# SW6124_A_B_C_MCU_SEG.net
KiCad netlist of a schematic drawn in Altium Designer
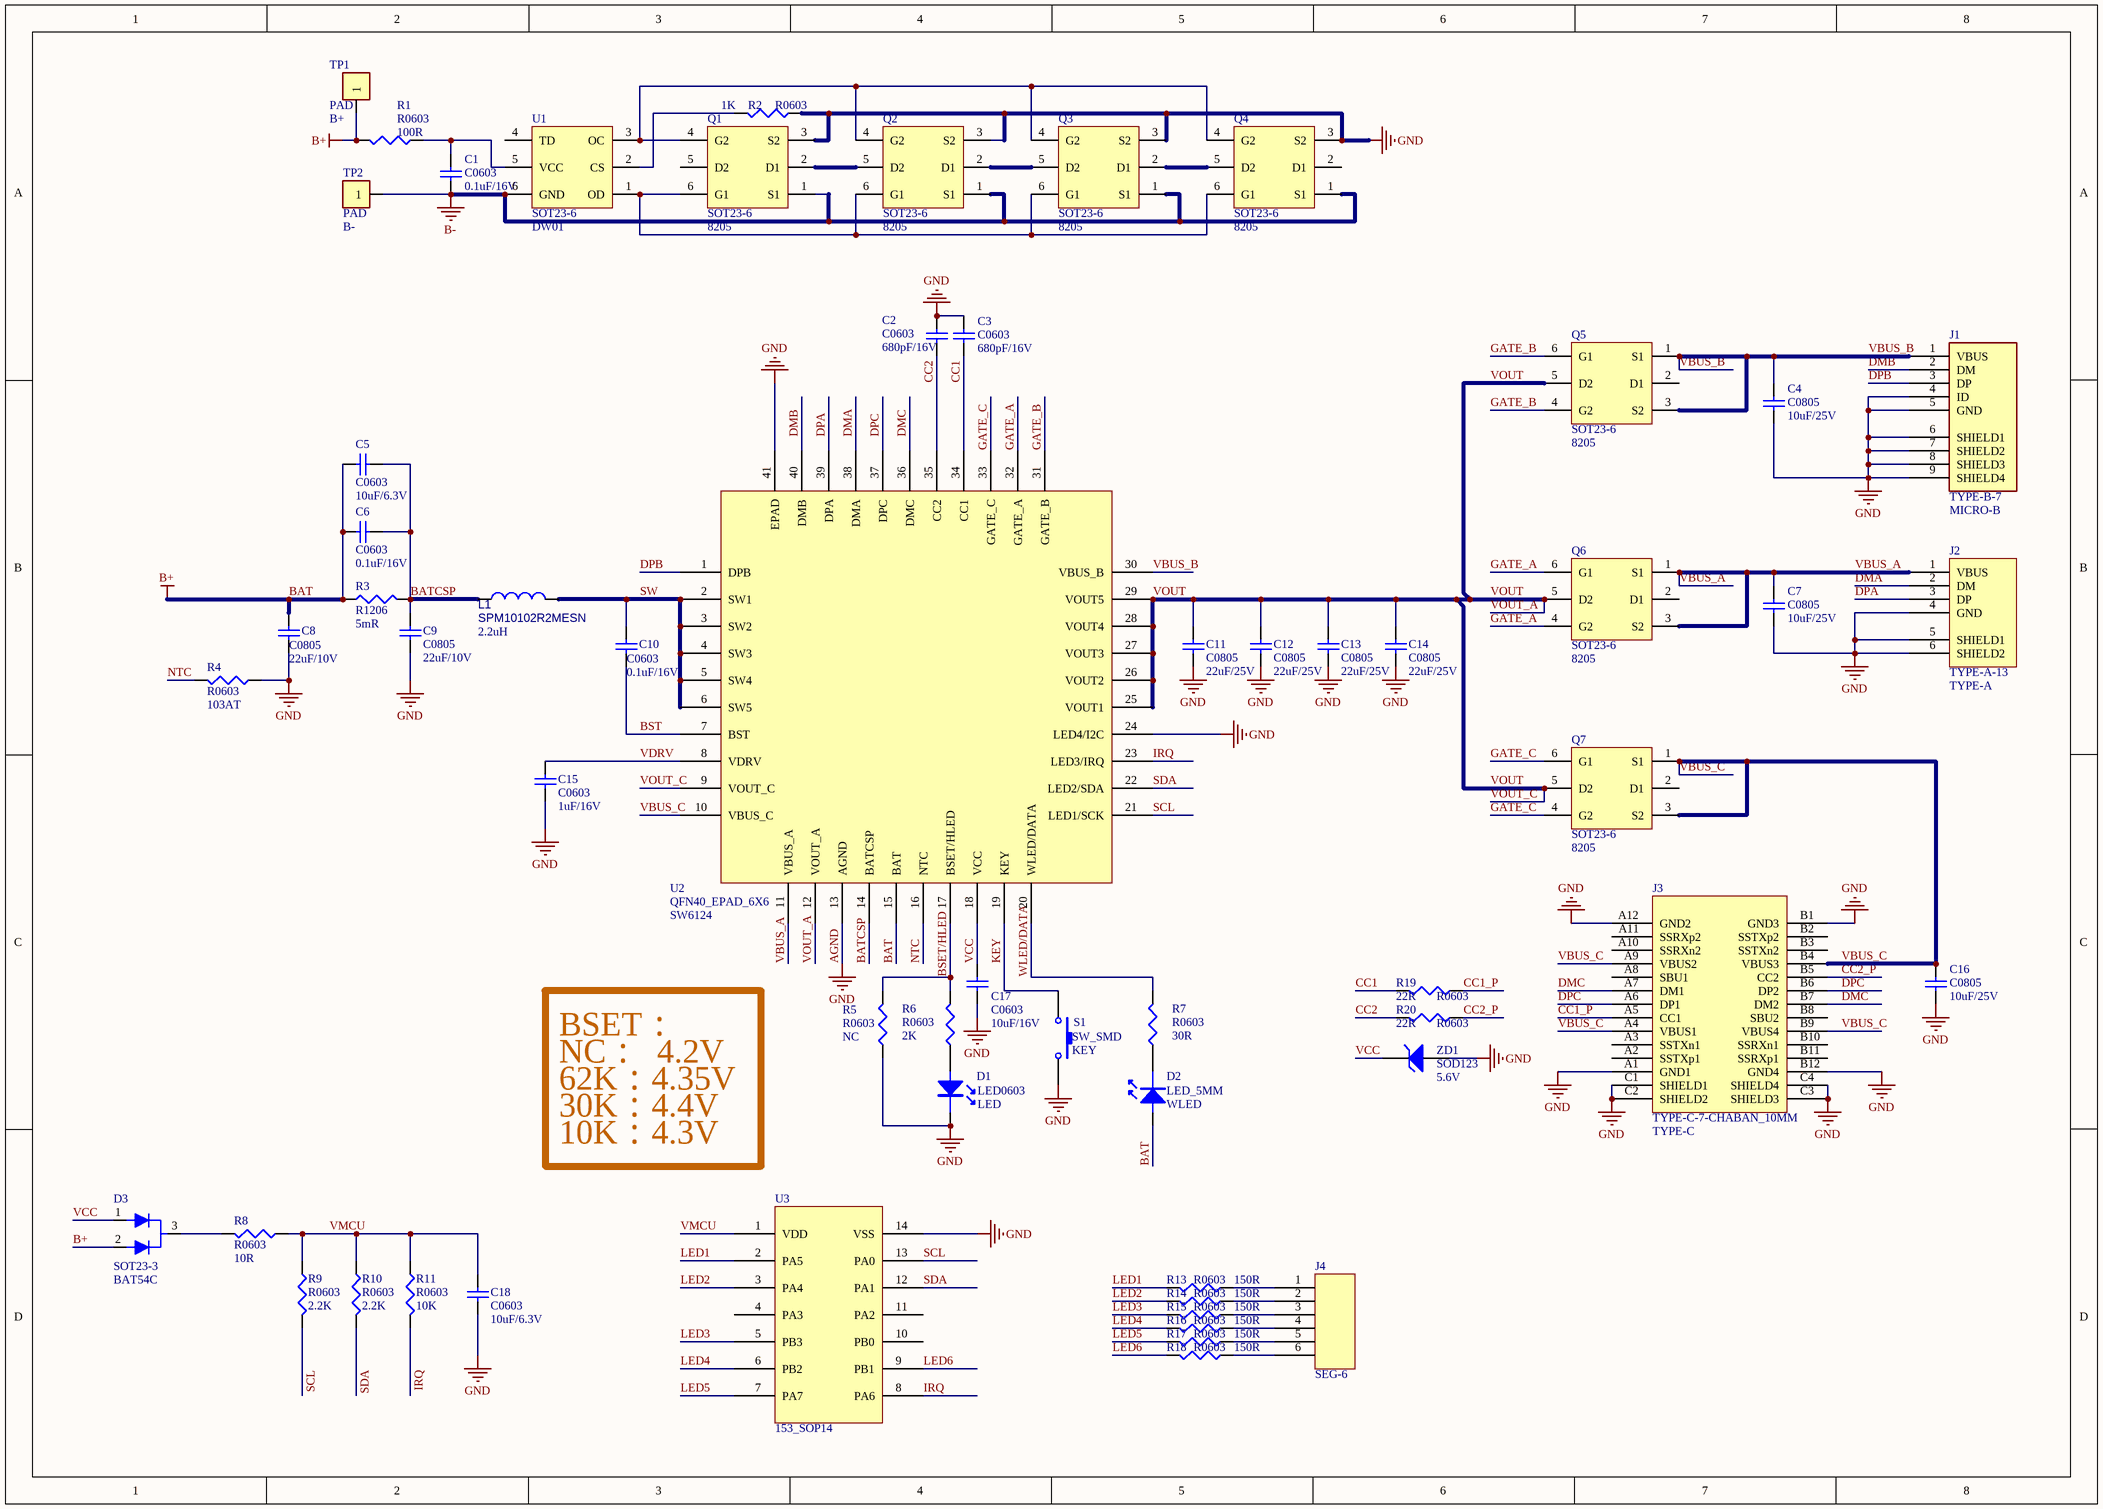
[diagram p0: SW6124+A+B+C+MCU+SEG.SchDoc]

(export (version "E")
  (design (tool "Eeschema 10.0.6"))
  (components
    (comp (ref "C1")
      (value "C0603")
      (footprint "C0603")
      (description "Capacitor")
      (fields (field (name "ALTIUM_VALUE") "0.1uF/16V") (field (name "PUBLISHER") "Altium Limited"))
      (libsource (lib "*") (part "Cap"))
    )
    (comp (ref "C2")
      (value "C0603")
      (footprint "C0603")
      (description "Capacitor")
      (fields (field (name "ALTIUM_VALUE") "680pF/16V") (field (name "PUBLISHER") "Altium Limited"))
      (libsource (lib "*") (part "CAP0603"))
    )
    (comp (ref "C3")
      (value "C0603")
      (footprint "C0603")
      (description "Capacitor")
      (fields (field (name "ALTIUM_VALUE") "680pF/16V") (field (name "PUBLISHER") "Altium Limited"))
      (libsource (lib "*") (part "CAP0603"))
    )
    (comp (ref "C4")
      (value "C0805")
      (footprint "C0805")
      (description "Capacitor")
      (fields (field (name "ALTIUM_VALUE") "10uF/25V") (field (name "PUBLISHER") "Altium Limited"))
      (libsource (lib "*") (part "CAP0603"))
    )
    (comp (ref "C5")
      (value "C0603")
      (footprint "C0603")
      (description "Capacitor")
      (fields (field (name "ALTIUM_VALUE") "10uF/6.3V") (field (name "PUBLISHER") "Altium Limited"))
      (libsource (lib "*") (part "CAP0603"))
    )
    (comp (ref "C6")
      (value "C0603")
      (footprint "C0603")
      (description "Capacitor")
      (fields (field (name "ALTIUM_VALUE") "0.1uF/16V") (field (name "PUBLISHER") "Altium Limited"))
      (libsource (lib "*") (part "CAP0603"))
    )
    (comp (ref "C7")
      (value "C0805")
      (footprint "C0805")
      (description "Capacitor")
      (fields (field (name "ALTIUM_VALUE") "10uF/25V") (field (name "PUBLISHER") "Altium Limited"))
      (libsource (lib "*") (part "CAP0603"))
    )
    (comp (ref "C8")
      (value "C0805")
      (footprint "C0805")
      (description "Capacitor")
      (fields (field (name "ALTIUM_VALUE") "22uF/10V") (field (name "PUBLISHER") "Altium Limited"))
      (libsource (lib "*") (part "CAP0805"))
    )
    (comp (ref "C9")
      (value "C0805")
      (footprint "C0805")
      (description "Capacitor")
      (fields (field (name "ALTIUM_VALUE") "22uF/10V") (field (name "PUBLISHER") "Altium Limited"))
      (libsource (lib "*") (part "CAP0805"))
    )
    (comp (ref "C10")
      (value "C0603")
      (footprint "C0603")
      (description "Capacitor")
      (fields (field (name "ALTIUM_VALUE") "0.1uF/16V") (field (name "PUBLISHER") "Altium Limited"))
      (libsource (lib "*") (part "CAP0603"))
    )
    (comp (ref "C11")
      (value "C0805")
      (footprint "C0805")
      (description "Capacitor")
      (fields (field (name "ALTIUM_VALUE") "22uF/25V") (field (name "PUBLISHER") "Altium Limited"))
      (libsource (lib "*") (part "CAP0805"))
    )
    (comp (ref "C12")
      (value "C0805")
      (footprint "C0805")
      (description "Capacitor")
      (fields (field (name "ALTIUM_VALUE") "22uF/25V") (field (name "PUBLISHER") "Altium Limited"))
      (libsource (lib "*") (part "CAP0805"))
    )
    (comp (ref "C13")
      (value "C0805")
      (footprint "C0805")
      (description "Capacitor")
      (fields (field (name "ALTIUM_VALUE") "22uF/25V") (field (name "PUBLISHER") "Altium Limited"))
      (libsource (lib "*") (part "CAP0805"))
    )
    (comp (ref "C14")
      (value "C0805")
      (footprint "C0805")
      (description "Capacitor")
      (fields (field (name "ALTIUM_VALUE") "22uF/25V") (field (name "PUBLISHER") "Altium Limited"))
      (libsource (lib "*") (part "CAP0805"))
    )
    (comp (ref "C15")
      (value "C0603")
      (footprint "C0603")
      (description "Capacitor")
      (fields (field (name "ALTIUM_VALUE") "1uF/16V") (field (name "PUBLISHER") "Altium Limited"))
      (libsource (lib "*") (part "CAP0603"))
    )
    (comp (ref "C16")
      (value "C0805")
      (footprint "C0805")
      (description "Capacitor")
      (fields (field (name "ALTIUM_VALUE") "10uF/25V") (field (name "PUBLISHER") "Altium Limited"))
      (libsource (lib "*") (part "CAP0603"))
    )
    (comp (ref "C17")
      (value "C0603")
      (footprint "C0603")
      (description "Capacitor")
      (fields (field (name "ALTIUM_VALUE") "10uF/16V") (field (name "PUBLISHER") "Altium Limited"))
      (libsource (lib "*") (part "CAP0603"))
    )
    (comp (ref "C18")
      (value "C0603")
      (footprint "C0603")
      (description "Capacitor")
      (fields (field (name "ALTIUM_VALUE") "10uF/6.3V") (field (name "PUBLISHER") "Altium Limited"))
      (libsource (lib "*") (part "CAP0603"))
    )
    (comp (ref "D1") (value "LED") (footprint "LED0603") (libsource (lib "*") (part "LED")))
    (comp (ref "D2")
      (value "WLED")
      (footprint "LED_5MM")
      (fields (field (name "FOOTPRINF") "LED_5MM") (field (name "Comment") "LED_5MM"))
      (libsource (lib "*") (part "LED"))
    )
    (comp (ref "D3") (value "BAT54C") (footprint "SOT23-3") (libsource (lib "Schlib1-2012") (part "D3")))
    (comp (ref "J1")
      (value "MICRO-B")
      (footprint "TYPE-B-7")
      (fields (field (name "FOOTPRINTF") "TYPE-B-7") (field (name "Comment") "USB_MICRO_B"))
      (libsource (lib "*") (part "USB_MICRO_B"))
    )
    (comp (ref "J2")
      (value "TYPE-A")
      (footprint "TYPE-A-13")
      (fields (field (name "FOOTPRINF") "TYPE-A-13") (field (name "Comment") "TYPE-A-1"))
      (libsource (lib "*") (part "TYPE-A-1"))
    )
    (comp (ref "J3")
      (value "TYPE-C")
      (footprint "TYPE-C-7-CHABAN_10MM")
      (libsource (lib "*") (part "TYPE-C"))
    )
    (comp (ref "J4") (value "SEG-6") (libsource (lib "TEST") (part "LCD-6")))
    (comp (ref "L1")
      (value "SPM10102R2MESN")
      (footprint "INDUCTOR_SPM1010")
      (fields (field (name "ALTIUM_VALUE") "2.2uH"))
      (libsource (lib "*") (part "INDUCTOR"))
    )
    (comp (ref "Q1")
      (value "8205")
      (footprint "SOT23-6")
      (fields (field (name "FOOTPRINF") "SOT23-6"))
      (libsource (lib "*") (part "8205B"))
    )
    (comp (ref "Q2")
      (value "8205")
      (footprint "SOT23-6")
      (fields (field (name "FOOTPRINF") "SOT23-6"))
      (libsource (lib "*") (part "8205B"))
    )
    (comp (ref "Q3")
      (value "8205")
      (footprint "SOT23-6")
      (fields (field (name "FOOTPRINF") "SOT23-6"))
      (libsource (lib "*") (part "8205B"))
    )
    (comp (ref "Q4")
      (value "8205")
      (footprint "SOT23-6")
      (fields (field (name "FOOTPRINF") "SOT23-6"))
      (libsource (lib "*") (part "8205B"))
    )
    (comp (ref "Q5")
      (value "8205")
      (footprint "SOT23-6")
      (fields (field (name "FOOTPRINF") "SOT23-6"))
      (libsource (lib "") (part "8205B_1"))
    )
    (comp (ref "Q6")
      (value "8205")
      (footprint "SOT23-6")
      (fields (field (name "FOOTPRINF") "SOT23-6"))
      (libsource (lib "") (part "8205B_1"))
    )
    (comp (ref "Q7")
      (value "8205")
      (footprint "SOT23-6")
      (fields (field (name "FOOTPRINF") "SOT23-6"))
      (libsource (lib "") (part "8205B_1"))
    )
    (comp (ref "R1")
      (value "R0603")
      (footprint "R0603")
      (description "Resistor")
      (fields (field (name "ALTIUM_VALUE") "100R") (field (name "PUBLISHER") "Altium Limited"))
      (libsource (lib "*") (part "Res3"))
    )
    (comp (ref "R2")
      (value "R0603")
      (footprint "R0603")
      (description "Resistor")
      (fields (field (name "ALTIUM_VALUE") "1K") (field (name "PUBLISHER") "Altium Limited"))
      (libsource (lib "*") (part "Res3"))
    )
    (comp (ref "R3")
      (value "R1206")
      (footprint "R1206")
      (description "Resistor")
      (fields (field (name "ALTIUM_VALUE") "5mR") (field (name "PUBLISHER") "Altium Limited"))
      (libsource (lib "*") (part "RES"))
    )
    (comp (ref "R4")
      (value "R0603")
      (footprint "R0603")
      (description "Resistor")
      (fields (field (name "ALTIUM_VALUE") "103AT") (field (name "PUBLISHER") "Altium Limited"))
      (libsource (lib "*") (part "RES"))
    )
    (comp (ref "R5")
      (value "R0603")
      (footprint "R0603")
      (description "Resistor")
      (fields (field (name "ALTIUM_VALUE") "NC") (field (name "PUBLISHER") "Altium Limited"))
      (libsource (lib "*") (part "RES"))
    )
    (comp (ref "R6")
      (value "R0603")
      (footprint "R0603")
      (description "Resistor")
      (fields (field (name "ALTIUM_VALUE") "2K") (field (name "PUBLISHER") "Altium Limited"))
      (libsource (lib "*") (part "RES"))
    )
    (comp (ref "R7")
      (value "R0603")
      (footprint "R0603")
      (description "Resistor")
      (fields (field (name "ALTIUM_VALUE") "30R") (field (name "PUBLISHER") "Altium Limited"))
      (libsource (lib "*") (part "RES"))
    )
    (comp (ref "R8")
      (value "R0603")
      (footprint "R0603")
      (description "Resistor")
      (fields (field (name "ALTIUM_VALUE") "10R") (field (name "PUBLISHER") "Altium Limited"))
      (libsource (lib "*") (part "RES"))
    )
    (comp (ref "R9")
      (value "R0603")
      (footprint "R0603")
      (description "Resistor")
      (fields (field (name "ALTIUM_VALUE") "2.2K") (field (name "PUBLISHER") "Altium Limited"))
      (libsource (lib "*") (part "RES"))
    )
    (comp (ref "R10")
      (value "R0603")
      (footprint "R0603")
      (description "Resistor")
      (fields (field (name "ALTIUM_VALUE") "2.2K") (field (name "PUBLISHER") "Altium Limited"))
      (libsource (lib "*") (part "RES"))
    )
    (comp (ref "R11")
      (value "R0603")
      (footprint "R0603")
      (description "Resistor")
      (fields (field (name "ALTIUM_VALUE") "10K") (field (name "PUBLISHER") "Altium Limited"))
      (libsource (lib "*") (part "RES"))
    )
    (comp (ref "R13")
      (value "R0603")
      (footprint "R0603")
      (description "Resistor")
      (fields (field (name "ALTIUM_VALUE") "150R") (field (name "PUBLISHER") "Altium Limited"))
      (libsource (lib "*") (part "RES"))
    )
    (comp (ref "R14")
      (value "R0603")
      (footprint "R0603")
      (description "Resistor")
      (fields (field (name "ALTIUM_VALUE") "150R") (field (name "PUBLISHER") "Altium Limited"))
      (libsource (lib "*") (part "RES"))
    )
    (comp (ref "R15")
      (value "R0603")
      (footprint "R0603")
      (description "Resistor")
      (fields (field (name "ALTIUM_VALUE") "150R") (field (name "PUBLISHER") "Altium Limited"))
      (libsource (lib "*") (part "RES"))
    )
    (comp (ref "R16")
      (value "R0603")
      (footprint "R0603")
      (description "Resistor")
      (fields (field (name "ALTIUM_VALUE") "150R") (field (name "PUBLISHER") "Altium Limited"))
      (libsource (lib "*") (part "RES"))
    )
    (comp (ref "R17")
      (value "R0603")
      (footprint "R0603")
      (description "Resistor")
      (fields (field (name "ALTIUM_VALUE") "150R") (field (name "PUBLISHER") "Altium Limited"))
      (libsource (lib "*") (part "RES"))
    )
    (comp (ref "R18")
      (value "R0603")
      (footprint "R0603")
      (description "Resistor")
      (fields (field (name "ALTIUM_VALUE") "150R") (field (name "PUBLISHER") "Altium Limited"))
      (libsource (lib "*") (part "RES"))
    )
    (comp (ref "R19")
      (value "R0603")
      (footprint "R0603")
      (description "Resistor")
      (fields (field (name "ALTIUM_VALUE") "22R") (field (name "PUBLISHER") "Altium Limited"))
      (libsource (lib "*") (part "RES"))
    )
    (comp (ref "R20")
      (value "R0603")
      (footprint "R0603")
      (description "Resistor")
      (fields (field (name "ALTIUM_VALUE") "22R") (field (name "PUBLISHER") "Altium Limited"))
      (libsource (lib "*") (part "RES"))
    )
    (comp (ref "S1")
      (value "KEY")
      (footprint "SW_SMD")
      (fields (field (name "FOOTPRINF") "SW_SMD"))
      (libsource (lib "*") (part "SW K"))
    )
    (comp (ref "TP1") (value "B+") (footprint "PAD") (libsource (lib "*") (part "Test Point")))
    (comp (ref "TP2") (value "B-") (footprint "PAD") (libsource (lib "") (part "Test Point_1")))
    (comp (ref "U1")
      (value "DW01")
      (footprint "SOT23-6")
      (fields (field (name "FOOTPRINF") "SOT23-6"))
      (libsource (lib "*") (part "DW01"))
    )
    (comp (ref "U2")
      (value "SW6124")
      (footprint "QFN40_EPAD_6X6")
      (libsource (lib "TEST") (part "SW6106_AFC"))
    )
    (comp (ref "U3") (value "153_SOP14") (libsource (lib "TEST") (part "153_SOP14")))
    (comp (ref "ZD1")
      (value "SOD123")
      (footprint "SOD-123")
      (description "Zener Diode")
      (fields (field (name "ALTIUM_UNNAMED_1") "5.6V"))
      (libsource (lib "Miscellaneous Devices") (part "D Zener"))
    )
  )
  (nets
    (net (code "1") (name "/BATCSP") (class "Default")
      (node (ref "C5") (pin "2") (pinfunction "2_2") (pintype "passive"))
      (node (ref "C6") (pin "2") (pinfunction "2_2") (pintype "passive"))
      (node (ref "C9") (pin "2") (pinfunction "2_2") (pintype "passive"))
      (node (ref "L1") (pin "1") (pinfunction "1_1") (pintype "passive"))
      (node (ref "R3") (pin "2") (pinfunction "2_2") (pintype "passive"))
      (node (ref "U2") (pin "14") (pinfunction "BATCSP_14") (pintype "passive"))
    )
    (net (code "2") (name "/BSET{slash}HLED") (class "Default")
      (node (ref "R5") (pin "2") (pinfunction "2_2") (pintype "passive"))
      (node (ref "R6") (pin "2") (pinfunction "2_2") (pintype "passive"))
      (node (ref "U2") (pin "17") (pinfunction "BSET/HLED_17") (pintype "passive"))
    )
    (net (code "3") (name "/BST") (class "Default")
      (node (ref "C10") (pin "1") (pinfunction "1_1") (pintype "passive"))
      (node (ref "U2") (pin "7") (pinfunction "BST_7") (pintype "passive"))
    )
    (net (code "4") (name "/CC1") (class "Default")
      (node (ref "C3") (pin "1") (pinfunction "1_1") (pintype "passive"))
      (node (ref "R19") (pin "2") (pinfunction "2_2") (pintype "passive"))
      (node (ref "U2") (pin "34") (pinfunction "CC1_34") (pintype "passive"))
    )
    (net (code "5") (name "/CC1_P") (class "Default")
      (node (ref "J3") (pin "A5") (pinfunction "CC1_A5") (pintype "passive"))
      (node (ref "R19") (pin "1") (pinfunction "1_1") (pintype "passive"))
    )
    (net (code "6") (name "/CC2") (class "Default")
      (node (ref "C2") (pin "1") (pinfunction "1_1") (pintype "passive"))
      (node (ref "R20") (pin "2") (pinfunction "2_2") (pintype "passive"))
      (node (ref "U2") (pin "35") (pinfunction "CC2_35") (pintype "passive"))
    )
    (net (code "7") (name "/CC2_P") (class "Default")
      (node (ref "J3") (pin "B5") (pinfunction "CC2_B5") (pintype "passive"))
      (node (ref "R20") (pin "1") (pinfunction "1_1") (pintype "passive"))
    )
    (net (code "8") (name "/DMA") (class "Default")
      (node (ref "J2") (pin "2") (pinfunction "DM_2") (pintype "passive"))
      (node (ref "U2") (pin "38") (pinfunction "DMA_38") (pintype "passive"))
    )
    (net (code "9") (name "/DMB") (class "Default")
      (node (ref "J1") (pin "2") (pinfunction "DM_2") (pintype "passive"))
      (node (ref "U2") (pin "40") (pinfunction "DMB_40") (pintype "passive"))
    )
    (net (code "10") (name "/DMC") (class "Default")
      (node (ref "J3") (pin "A7") (pinfunction "DM1_A7") (pintype "passive"))
      (node (ref "J3") (pin "B7") (pinfunction "DM2_B7") (pintype "passive"))
      (node (ref "U2") (pin "36") (pinfunction "DMC_36") (pintype "passive"))
    )
    (net (code "11") (name "/DPA") (class "Default")
      (node (ref "J2") (pin "3") (pinfunction "DP_3") (pintype "passive"))
      (node (ref "U2") (pin "39") (pinfunction "DPA_39") (pintype "passive"))
    )
    (net (code "12") (name "/DPB") (class "Default")
      (node (ref "J1") (pin "3") (pinfunction "DP_3") (pintype "passive"))
      (node (ref "U2") (pin "1") (pinfunction "DPB_1") (pintype "passive"))
    )
    (net (code "13") (name "/DPC") (class "Default")
      (node (ref "J3") (pin "A6") (pinfunction "DP1_A6") (pintype "passive"))
      (node (ref "J3") (pin "B6") (pinfunction "DP2_B6") (pintype "passive"))
      (node (ref "U2") (pin "37") (pinfunction "DPC_37") (pintype "passive"))
    )
    (net (code "14") (name "/GATE_A") (class "Default")
      (node (ref "Q6") (pin "4") (pinfunction "G2_4") (pintype "passive"))
      (node (ref "Q6") (pin "6") (pinfunction "G1_6") (pintype "passive"))
      (node (ref "U2") (pin "32") (pinfunction "GATE_A_32") (pintype "passive"))
    )
    (net (code "15") (name "/GATE_B") (class "Default")
      (node (ref "Q5") (pin "4") (pinfunction "G2_4") (pintype "passive"))
      (node (ref "Q5") (pin "6") (pinfunction "G1_6") (pintype "passive"))
      (node (ref "U2") (pin "31") (pinfunction "GATE_B_31") (pintype "passive"))
    )
    (net (code "16") (name "/GATE_C") (class "Default")
      (node (ref "Q7") (pin "4") (pinfunction "G2_4") (pintype "passive"))
      (node (ref "Q7") (pin "6") (pinfunction "G1_6") (pintype "passive"))
      (node (ref "U2") (pin "33") (pinfunction "GATE_C_33") (pintype "passive"))
    )
    (net (code "17") (name "/IRQ") (class "Default")
      (node (ref "R11") (pin "2") (pinfunction "2_2") (pintype "passive"))
      (node (ref "U2") (pin "23") (pinfunction "LED3/IRQ_23") (pintype "passive"))
      (node (ref "U3") (pin "8") (pinfunction "PA6_8") (pintype "passive"))
    )
    (net (code "18") (name "/KEY") (class "Default")
      (node (ref "S1") (pin "1") (pinfunction "1_1") (pintype "passive"))
      (node (ref "U2") (pin "19") (pinfunction "KEY_19") (pintype "passive"))
    )
    (net (code "19") (name "/LED1") (class "Default")
      (node (ref "R13") (pin "2") (pinfunction "2_2") (pintype "passive"))
      (node (ref "U3") (pin "2") (pinfunction "PA5_2") (pintype "passive"))
    )
    (net (code "20") (name "/LED2") (class "Default")
      (node (ref "R14") (pin "2") (pinfunction "2_2") (pintype "passive"))
      (node (ref "U3") (pin "3") (pinfunction "PA4_3") (pintype "passive"))
    )
    (net (code "21") (name "/LED3") (class "Default")
      (node (ref "R15") (pin "2") (pinfunction "2_2") (pintype "passive"))
      (node (ref "U3") (pin "5") (pinfunction "PB3_5") (pintype "passive"))
    )
    (net (code "22") (name "/LED4") (class "Default")
      (node (ref "R16") (pin "2") (pinfunction "2_2") (pintype "passive"))
      (node (ref "U3") (pin "6") (pinfunction "PB2_6") (pintype "passive"))
    )
    (net (code "23") (name "/LED5") (class "Default")
      (node (ref "R17") (pin "2") (pinfunction "2_2") (pintype "passive"))
      (node (ref "U3") (pin "7") (pinfunction "PA7_7") (pintype "passive"))
    )
    (net (code "24") (name "/LED6") (class "Default")
      (node (ref "R18") (pin "2") (pinfunction "2_2") (pintype "passive"))
      (node (ref "U3") (pin "9") (pinfunction "PB1_9") (pintype "passive"))
    )
    (net (code "25") (name "/NTC") (class "Default")
      (node (ref "R4") (pin "2") (pinfunction "2_2") (pintype "passive"))
      (node (ref "U2") (pin "16") (pinfunction "NTC_16") (pintype "passive"))
    )
    (net (code "26") (name "/SCL") (class "Default")
      (node (ref "R9") (pin "2") (pinfunction "2_2") (pintype "passive"))
      (node (ref "U2") (pin "21") (pinfunction "LED1/SCK_21") (pintype "passive"))
      (node (ref "U3") (pin "13") (pinfunction "PA0_13") (pintype "passive"))
    )
    (net (code "27") (name "/SDA") (class "Default")
      (node (ref "R10") (pin "2") (pinfunction "2_2") (pintype "passive"))
      (node (ref "U2") (pin "22") (pinfunction "LED2/SDA_22") (pintype "passive"))
      (node (ref "U3") (pin "12") (pinfunction "PA1_12") (pintype "passive"))
    )
    (net (code "28") (name "/SW") (class "Default")
      (node (ref "C10") (pin "2") (pinfunction "2_2") (pintype "passive"))
      (node (ref "L1") (pin "2") (pinfunction "2_2") (pintype "passive"))
      (node (ref "U2") (pin "2") (pinfunction "SW1_2") (pintype "passive"))
      (node (ref "U2") (pin "3") (pinfunction "SW2_3") (pintype "passive"))
      (node (ref "U2") (pin "4") (pinfunction "SW3_4") (pintype "passive"))
      (node (ref "U2") (pin "5") (pinfunction "SW4_5") (pintype "passive"))
      (node (ref "U2") (pin "6") (pinfunction "SW5_6") (pintype "passive"))
    )
    (net (code "29") (name "/VBUS_A") (class "Default")
      (node (ref "C7") (pin "2") (pinfunction "2_2") (pintype "passive"))
      (node (ref "J2") (pin "1") (pinfunction "VBUS_1") (pintype "passive"))
      (node (ref "Q6") (pin "1") (pinfunction "S1_1") (pintype "passive"))
      (node (ref "Q6") (pin "3") (pinfunction "S2_3") (pintype "passive"))
      (node (ref "U2") (pin "11") (pinfunction "VBUS_A_11") (pintype "passive"))
    )
    (net (code "30") (name "/VBUS_B") (class "Default")
      (node (ref "C4") (pin "2") (pinfunction "2_2") (pintype "passive"))
      (node (ref "J1") (pin "1") (pinfunction "VBUS_1") (pintype "passive"))
      (node (ref "Q5") (pin "1") (pinfunction "S1_1") (pintype "passive"))
      (node (ref "Q5") (pin "3") (pinfunction "S2_3") (pintype "passive"))
      (node (ref "U2") (pin "30") (pinfunction "VBUS_B_30") (pintype "passive"))
    )
    (net (code "31") (name "/VBUS_C") (class "Default")
      (node (ref "C16") (pin "2") (pinfunction "2_2") (pintype "passive"))
      (node (ref "J3") (pin "A4") (pinfunction "VBUS1_A4") (pintype "passive"))
      (node (ref "J3") (pin "A9") (pinfunction "VBUS2_A9") (pintype "passive"))
      (node (ref "J3") (pin "B4") (pinfunction "VBUS3_B4") (pintype "passive"))
      (node (ref "J3") (pin "B9") (pinfunction "VBUS4_B9") (pintype "passive"))
      (node (ref "Q7") (pin "1") (pinfunction "S1_1") (pintype "passive"))
      (node (ref "Q7") (pin "3") (pinfunction "S2_3") (pintype "passive"))
      (node (ref "U2") (pin "10") (pinfunction "VBUS_C_10") (pintype "passive"))
    )
    (net (code "32") (name "/VCC") (class "Default")
      (node (ref "C17") (pin "2") (pinfunction "2_2") (pintype "passive"))
      (node (ref "D3") (pin "1") (pintype "passive"))
      (node (ref "U2") (pin "18") (pinfunction "VCC_18") (pintype "passive"))
      (node (ref "ZD1") (pin "2") (pinfunction "K_2") (pintype "passive"))
    )
    (net (code "33") (name "/VDRV") (class "Default")
      (node (ref "C15") (pin "2") (pinfunction "2_2") (pintype "passive"))
      (node (ref "U2") (pin "8") (pinfunction "VDRV_8") (pintype "passive"))
    )
    (net (code "34") (name "/VMCU") (class "Default")
      (node (ref "C18") (pin "1") (pinfunction "1_1") (pintype "passive"))
      (node (ref "R10") (pin "1") (pinfunction "1_1") (pintype "passive"))
      (node (ref "R11") (pin "1") (pinfunction "1_1") (pintype "passive"))
      (node (ref "R8") (pin "1") (pinfunction "1_1") (pintype "passive"))
      (node (ref "R9") (pin "1") (pinfunction "1_1") (pintype "passive"))
      (node (ref "U3") (pin "1") (pinfunction "VDD_1") (pintype "passive"))
    )
    (net (code "35") (name "/VOUT") (class "Default")
      (node (ref "C11") (pin "2") (pinfunction "2_2") (pintype "passive"))
      (node (ref "C12") (pin "2") (pinfunction "2_2") (pintype "passive"))
      (node (ref "C13") (pin "2") (pinfunction "2_2") (pintype "passive"))
      (node (ref "C14") (pin "2") (pinfunction "2_2") (pintype "passive"))
      (node (ref "Q5") (pin "5") (pinfunction "D2_5") (pintype "passive"))
      (node (ref "Q6") (pin "5") (pinfunction "D2_5") (pintype "passive"))
      (node (ref "Q7") (pin "5") (pinfunction "D2_5") (pintype "passive"))
      (node (ref "U2") (pin "12") (pinfunction "VOUT_A_12") (pintype "passive"))
      (node (ref "U2") (pin "25") (pinfunction "VOUT1_25") (pintype "passive"))
      (node (ref "U2") (pin "26") (pinfunction "VOUT2_26") (pintype "passive"))
      (node (ref "U2") (pin "27") (pinfunction "VOUT3_27") (pintype "passive"))
      (node (ref "U2") (pin "28") (pinfunction "VOUT4_28") (pintype "passive"))
      (node (ref "U2") (pin "29") (pinfunction "VOUT5_29") (pintype "passive"))
      (node (ref "U2") (pin "9") (pinfunction "VOUT_C_9") (pintype "passive"))
    )
    (net (code "36") (name "/WLED{slash}DATA") (class "Default")
      (node (ref "R7") (pin "2") (pinfunction "2_2") (pintype "passive"))
      (node (ref "U2") (pin "20") (pinfunction "WLED/DATA_20") (pintype "passive"))
    )
    (net (code "37") (name "B+") (class "Default")
      (node (ref "C5") (pin "1") (pinfunction "1_1") (pintype "passive"))
      (node (ref "C6") (pin "1") (pinfunction "1_1") (pintype "passive"))
      (node (ref "C8") (pin "2") (pinfunction "2_2") (pintype "passive"))
      (node (ref "D2") (pin "1") (pinfunction "A_1") (pintype "passive"))
      (node (ref "D3") (pin "2") (pintype "passive"))
      (node (ref "R1") (pin "2") (pinfunction "2_2") (pintype "passive"))
      (node (ref "R3") (pin "1") (pinfunction "1_1") (pintype "passive"))
      (node (ref "TP1") (pin "1") (pinfunction "1_1") (pintype "passive"))
      (node (ref "U2") (pin "15") (pinfunction "BAT_15") (pintype "passive"))
    )
    (net (code "38") (name "B-") (class "Default")
      (node (ref "C1") (pin "1") (pinfunction "1_1") (pintype "passive"))
      (node (ref "Q1") (pin "1") (pinfunction "S1_1") (pintype "passive"))
      (node (ref "Q2") (pin "1") (pinfunction "S1_1") (pintype "passive"))
      (node (ref "Q3") (pin "1") (pinfunction "S1_1") (pintype "passive"))
      (node (ref "Q4") (pin "1") (pinfunction "S1_1") (pintype "passive"))
      (node (ref "TP2") (pin "1") (pinfunction "1_1") (pintype "passive"))
      (node (ref "U1") (pin "6") (pinfunction "GND_6") (pintype "passive"))
    )
    (net (code "39") (name "GND") (class "Default")
      (node (ref "C11") (pin "1") (pinfunction "1_1") (pintype "passive"))
      (node (ref "C12") (pin "1") (pinfunction "1_1") (pintype "passive"))
      (node (ref "C13") (pin "1") (pinfunction "1_1") (pintype "passive"))
      (node (ref "C14") (pin "1") (pinfunction "1_1") (pintype "passive"))
      (node (ref "C15") (pin "1") (pinfunction "1_1") (pintype "passive"))
      (node (ref "C16") (pin "1") (pinfunction "1_1") (pintype "passive"))
      (node (ref "C17") (pin "1") (pinfunction "1_1") (pintype "passive"))
      (node (ref "C18") (pin "2") (pinfunction "2_2") (pintype "passive"))
      (node (ref "C2") (pin "2") (pinfunction "2_2") (pintype "passive"))
      (node (ref "C3") (pin "2") (pinfunction "2_2") (pintype "passive"))
      (node (ref "C4") (pin "1") (pinfunction "1_1") (pintype "passive"))
      (node (ref "C7") (pin "1") (pinfunction "1_1") (pintype "passive"))
      (node (ref "C8") (pin "1") (pinfunction "1_1") (pintype "passive"))
      (node (ref "C9") (pin "1") (pinfunction "1_1") (pintype "passive"))
      (node (ref "D1") (pin "2") (pinfunction "K_2") (pintype "passive"))
      (node (ref "J1") (pin "4") (pinfunction "ID_4") (pintype "passive"))
      (node (ref "J1") (pin "5") (pinfunction "GND_5") (pintype "passive"))
      (node (ref "J1") (pin "6") (pinfunction "SHIELD1_6") (pintype "passive"))
      (node (ref "J1") (pin "7") (pinfunction "SHIELD2_7") (pintype "passive"))
      (node (ref "J1") (pin "8") (pinfunction "SHIELD3_8") (pintype "passive"))
      (node (ref "J1") (pin "9") (pinfunction "SHIELD4_9") (pintype "passive"))
      (node (ref "J2") (pin "4") (pinfunction "GND_4") (pintype "passive"))
      (node (ref "J2") (pin "5") (pinfunction "SHIELD1_5") (pintype "passive"))
      (node (ref "J2") (pin "6") (pinfunction "SHIELD2_6") (pintype "passive"))
      (node (ref "J3") (pin "A1") (pinfunction "GND1_A1") (pintype "passive"))
      (node (ref "J3") (pin "A12") (pinfunction "GND2_A12") (pintype "passive"))
      (node (ref "J3") (pin "B1") (pinfunction "GND3_B1") (pintype "passive"))
      (node (ref "J3") (pin "B12") (pinfunction "GND4_B12") (pintype "passive"))
      (node (ref "J3") (pin "C1") (pinfunction "SHIELD1_C1") (pintype "passive"))
      (node (ref "J3") (pin "C2") (pinfunction "SHIELD2_C2") (pintype "passive"))
      (node (ref "J3") (pin "C3") (pinfunction "SHIELD3_C3") (pintype "passive"))
      (node (ref "J3") (pin "C4") (pinfunction "SHIELD4_C4") (pintype "passive"))
      (node (ref "Q1") (pin "3") (pinfunction "S2_3") (pintype "passive"))
      (node (ref "Q2") (pin "3") (pinfunction "S2_3") (pintype "passive"))
      (node (ref "Q3") (pin "3") (pinfunction "S2_3") (pintype "passive"))
      (node (ref "Q4") (pin "3") (pinfunction "S2_3") (pintype "passive"))
      (node (ref "R2") (pin "1") (pinfunction "1_1") (pintype "passive"))
      (node (ref "R4") (pin "1") (pinfunction "1_1") (pintype "passive"))
      (node (ref "R5") (pin "1") (pinfunction "1_1") (pintype "passive"))
      (node (ref "S1") (pin "2") (pinfunction "2_2") (pintype "passive"))
      (node (ref "U2") (pin "13") (pinfunction "AGND_13") (pintype "passive"))
      (node (ref "U2") (pin "24") (pinfunction "LED4/I2C_24") (pintype "passive"))
      (node (ref "U2") (pin "41") (pinfunction "EPAD_41") (pintype "passive"))
      (node (ref "U3") (pin "14") (pinfunction "VSS_14") (pintype "passive"))
      (node (ref "ZD1") (pin "1") (pinfunction "A_1") (pintype "passive"))
    )
    (net (code "40") (name "Net-(D1-A)") (class "Default")
      (node (ref "D1") (pin "1") (pinfunction "A_1") (pintype "passive"))
      (node (ref "R6") (pin "1") (pinfunction "1_1") (pintype "passive"))
    )
    (net (code "41") (name "Net-(D2-K)") (class "Default")
      (node (ref "D2") (pin "2") (pinfunction "K_2") (pintype "passive"))
      (node (ref "R7") (pin "1") (pinfunction "1_1") (pintype "passive"))
    )
    (net (code "42") (name "Net-(D3-Pad3)") (class "Default")
      (node (ref "D3") (pin "3") (pintype "passive"))
      (node (ref "R8") (pin "2") (pinfunction "2_2") (pintype "passive"))
    )
    (net (code "43") (name "Net-(J4-Pad1)") (class "Default")
      (node (ref "J4") (pin "1") (pinfunction "1_1") (pintype "passive"))
      (node (ref "R13") (pin "1") (pinfunction "1_1") (pintype "passive"))
    )
    (net (code "44") (name "Net-(J4-Pad2)") (class "Default")
      (node (ref "J4") (pin "2") (pinfunction "2_2") (pintype "passive"))
      (node (ref "R14") (pin "1") (pinfunction "1_1") (pintype "passive"))
    )
    (net (code "45") (name "Net-(J4-Pad3)") (class "Default")
      (node (ref "J4") (pin "3") (pinfunction "3_3") (pintype "passive"))
      (node (ref "R15") (pin "1") (pinfunction "1_1") (pintype "passive"))
    )
    (net (code "46") (name "Net-(J4-Pad4)") (class "Default")
      (node (ref "J4") (pin "4") (pinfunction "4_4") (pintype "passive"))
      (node (ref "R16") (pin "1") (pinfunction "1_1") (pintype "passive"))
    )
    (net (code "47") (name "Net-(J4-Pad5)") (class "Default")
      (node (ref "J4") (pin "5") (pinfunction "5_5") (pintype "passive"))
      (node (ref "R17") (pin "1") (pinfunction "1_1") (pintype "passive"))
    )
    (net (code "48") (name "Net-(J4-Pad6)") (class "Default")
      (node (ref "J4") (pin "6") (pinfunction "6_6") (pintype "passive"))
      (node (ref "R18") (pin "1") (pinfunction "1_1") (pintype "passive"))
    )
    (net (code "49") (name "Net-(Q1-D1)") (class "Default")
      (node (ref "Q1") (pin "2") (pinfunction "D1_2") (pintype "passive"))
      (node (ref "Q2") (pin "5") (pinfunction "D2_5") (pintype "passive"))
    )
    (net (code "50") (name "Net-(Q1-G1)") (class "Default")
      (node (ref "Q1") (pin "6") (pinfunction "G1_6") (pintype "passive"))
      (node (ref "Q2") (pin "6") (pinfunction "G1_6") (pintype "passive"))
      (node (ref "Q3") (pin "6") (pinfunction "G1_6") (pintype "passive"))
      (node (ref "Q4") (pin "6") (pinfunction "G1_6") (pintype "passive"))
      (node (ref "U1") (pin "1") (pinfunction "OD_1") (pintype "passive"))
    )
    (net (code "51") (name "Net-(Q1-G2)") (class "Default")
      (node (ref "Q1") (pin "4") (pinfunction "G2_4") (pintype "passive"))
      (node (ref "Q2") (pin "4") (pinfunction "G2_4") (pintype "passive"))
      (node (ref "Q3") (pin "4") (pinfunction "G2_4") (pintype "passive"))
      (node (ref "Q4") (pin "4") (pinfunction "G2_4") (pintype "passive"))
      (node (ref "U1") (pin "3") (pinfunction "OC_3") (pintype "passive"))
    )
    (net (code "52") (name "Net-(Q2-D1)") (class "Default")
      (node (ref "Q2") (pin "2") (pinfunction "D1_2") (pintype "passive"))
      (node (ref "Q3") (pin "5") (pinfunction "D2_5") (pintype "passive"))
    )
    (net (code "53") (name "Net-(Q3-D1)") (class "Default")
      (node (ref "Q3") (pin "2") (pinfunction "D1_2") (pintype "passive"))
      (node (ref "Q4") (pin "5") (pinfunction "D2_5") (pintype "passive"))
    )
    (net (code "54") (name "Net-(U1-CS)") (class "Default")
      (node (ref "R2") (pin "2") (pinfunction "2_2") (pintype "passive"))
      (node (ref "U1") (pin "2") (pinfunction "CS_2") (pintype "passive"))
    )
    (net (code "55") (name "Net-(U1-VCC)") (class "Default")
      (node (ref "C1") (pin "2") (pinfunction "2_2") (pintype "passive"))
      (node (ref "R1") (pin "1") (pinfunction "1_1") (pintype "passive"))
      (node (ref "U1") (pin "5") (pinfunction "VCC_5") (pintype "passive"))
    )
    (net (code "56") (name "unconnected-(J3-SBU1-PadA8)") (class "Default")
      (node (ref "J3") (pin "A8") (pinfunction "SBU1_A8") (pintype "passive"))
    )
    (net (code "57") (name "unconnected-(J3-SBU2-PadB8)") (class "Default")
      (node (ref "J3") (pin "B8") (pinfunction "SBU2_B8") (pintype "passive"))
    )
    (net (code "58") (name "unconnected-(J3-SSRXn1-PadB10)") (class "Default")
      (node (ref "J3") (pin "B10") (pinfunction "SSRXn1_B10") (pintype "passive"))
    )
    (net (code "59") (name "unconnected-(J3-SSRXn2-PadA10)") (class "Default")
      (node (ref "J3") (pin "A10") (pinfunction "SSRXn2_A10") (pintype "passive"))
    )
    (net (code "60") (name "unconnected-(J3-SSRXp1-PadB11)") (class "Default")
      (node (ref "J3") (pin "B11") (pinfunction "SSRXp1_B11") (pintype "passive"))
    )
    (net (code "61") (name "unconnected-(J3-SSRXp2-PadA11)") (class "Default")
      (node (ref "J3") (pin "A11") (pinfunction "SSRXp2_A11") (pintype "passive"))
    )
    (net (code "62") (name "unconnected-(J3-SSTXn1-PadA3)") (class "Default")
      (node (ref "J3") (pin "A3") (pinfunction "SSTXn1_A3") (pintype "passive"))
    )
    (net (code "63") (name "unconnected-(J3-SSTXn2-PadB3)") (class "Default")
      (node (ref "J3") (pin "B3") (pinfunction "SSTXn2_B3") (pintype "passive"))
    )
    (net (code "64") (name "unconnected-(J3-SSTXp1-PadA2)") (class "Default")
      (node (ref "J3") (pin "A2") (pinfunction "SSTXp1_A2") (pintype "passive"))
    )
    (net (code "65") (name "unconnected-(J3-SSTXp2-PadB2)") (class "Default")
      (node (ref "J3") (pin "B2") (pinfunction "SSTXp2_B2") (pintype "passive"))
    )
    (net (code "66") (name "unconnected-(Q1-D2-Pad5)") (class "Default")
      (node (ref "Q1") (pin "5") (pinfunction "D2_5") (pintype "passive"))
    )
    (net (code "67") (name "unconnected-(Q4-D1-Pad2)") (class "Default")
      (node (ref "Q4") (pin "2") (pinfunction "D1_2") (pintype "passive"))
    )
    (net (code "68") (name "unconnected-(Q5-D1-Pad2)") (class "Default")
      (node (ref "Q5") (pin "2") (pinfunction "D1_2") (pintype "passive"))
    )
    (net (code "69") (name "unconnected-(Q6-D1-Pad2)") (class "Default")
      (node (ref "Q6") (pin "2") (pinfunction "D1_2") (pintype "passive"))
    )
    (net (code "70") (name "unconnected-(Q7-D1-Pad2)") (class "Default")
      (node (ref "Q7") (pin "2") (pinfunction "D1_2") (pintype "passive"))
    )
    (net (code "71") (name "unconnected-(U1-TD-Pad4)") (class "Default")
      (node (ref "U1") (pin "4") (pinfunction "TD_4") (pintype "passive"))
    )
    (net (code "72") (name "unconnected-(U3-PA2-Pad11)") (class "Default")
      (node (ref "U3") (pin "11") (pinfunction "PA2_11") (pintype "passive"))
    )
    (net (code "73") (name "unconnected-(U3-PA3-Pad4)") (class "Default")
      (node (ref "U3") (pin "4") (pinfunction "PA3_4") (pintype "passive"))
    )
    (net (code "74") (name "unconnected-(U3-PB0-Pad10)") (class "Default")
      (node (ref "U3") (pin "10") (pinfunction "PB0_10") (pintype "passive"))
    )
  )
)
